# Digital_IO.net
KiCad netlist of a schematic drawn in Altium Designer
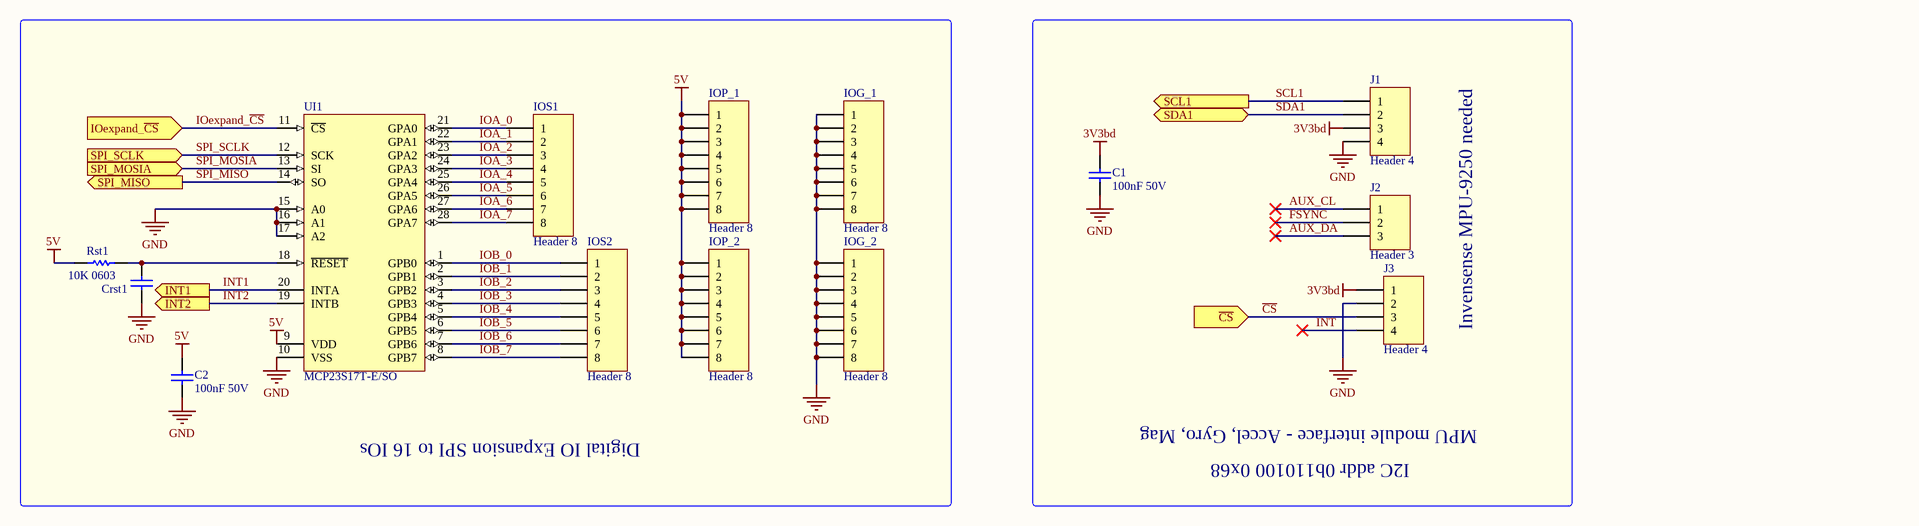
[diagram p0: Digital_IO.SchDoc]

(export (version "E")
  (design (tool "Eeschema 10.0.6"))
  (components
    (comp (ref "C1")
      (value "100nF 50V")
      (footprint "0603C_L")
      (fields
        (field (name "MANUFACTURER") "Yageo")
        (field (name "MANUFACTURER PART NUMBER") "CC0603ZRY5V9BB104")
        (field (name "TOLERANCE") "-20%, +80%")
      )
      (libsource (lib "WCT") (part "Cap101nF_50V_0603"))
    )
    (comp (ref "C2")
      (value "100nF 50V")
      (footprint "0603C_L")
      (fields
        (field (name "MANUFACTURER") "Yageo")
        (field (name "MANUFACTURER PART NUMBER") "CC0603ZRY5V9BB104")
        (field (name "TOLERANCE") "-20%, +80%")
      )
      (libsource (lib "WCT") (part "Cap101nF_50V_0603"))
    )
    (comp (ref "Crst1")
      (value "100nF 50V")
      (footprint "0603C_L")
      (fields
        (field (name "MANUFACTURER") "Yageo")
        (field (name "MANUFACTURER PART NUMBER") "CC0603ZRY5V9BB104")
        (field (name "TOLERANCE") "-20%, +80%")
      )
      (libsource (lib "WCT") (part "Cap100nF_50V_0603"))
    )
    (comp (ref "IOG_1")
      (value "Header 8")
      (footprint "HDR1X8")
      (description "Header, 8-Pin")
      (fields (field (name "PUBLISHER") "Altium Limited"))
      (libsource (lib "Miscellaneous Connectors") (part "Header 8"))
    )
    (comp (ref "IOG_2")
      (value "Header 8")
      (footprint "HDR1X8")
      (description "Header, 8-Pin")
      (fields (field (name "PUBLISHER") "Altium Limited"))
      (libsource (lib "Miscellaneous Connectors") (part "Header 8"))
    )
    (comp (ref "IOP_1")
      (value "Header 8")
      (footprint "HDR1X8")
      (description "Header, 8-Pin")
      (fields (field (name "PUBLISHER") "Altium Limited"))
      (libsource (lib "Miscellaneous Connectors") (part "Header 8"))
    )
    (comp (ref "IOP_2")
      (value "Header 8")
      (footprint "HDR1X8")
      (description "Header, 8-Pin")
      (fields (field (name "PUBLISHER") "Altium Limited"))
      (libsource (lib "Miscellaneous Connectors") (part "Header 8"))
    )
    (comp (ref "IOS1")
      (value "Header 8")
      (footprint "HDR1X8")
      (description "Header, 8-Pin")
      (fields (field (name "PUBLISHER") "Altium Limited"))
      (libsource (lib "Miscellaneous Connectors") (part "Header 8"))
    )
    (comp (ref "IOS2")
      (value "Header 8")
      (footprint "HDR1X8")
      (description "Header, 8-Pin")
      (fields (field (name "PUBLISHER") "Altium Limited"))
      (libsource (lib "Miscellaneous Connectors") (part "Header 8"))
    )
    (comp (ref "J1")
      (value "Header 4")
      (footprint "HDR1X4")
      (description "Header, 4-Pin")
      (fields (field (name "PUBLISHER") "Altium Limited"))
      (libsource (lib "Miscellaneous Connectors") (part "Header 4"))
    )
    (comp (ref "J2")
      (value "Header 3")
      (footprint "HDR1X3")
      (description "Header, 3-Pin")
      (fields (field (name "PUBLISHER") "Altium Limited"))
      (libsource (lib "Miscellaneous Connectors") (part "Header 3"))
    )
    (comp (ref "J3")
      (value "Header 4")
      (footprint "HDR1X4")
      (description "Header, 4-Pin")
      (fields (field (name "PUBLISHER") "Altium Limited"))
      (libsource (lib "Miscellaneous Connectors") (part "Header 4"))
    )
    (comp (ref "Rst1")
      (value "10K 0603")
      (footprint "0603_L")
      (fields
        (field (name "MANUFACTURER") "Panasonic Electronic Components")
        (field (name "MANUFACTURER PART NUMBER") "ERJ-3GEYJ102V")
        (field (name "TOLERANCE") "±5%")
      )
      (libsource (lib "WCT") (part "Res10K_0603"))
    )
    (comp (ref "UI1")
      (value "MCP23S17T-E/SO")
      (footprint "SOIC-SO28_L")
      (description "16-Bit I/O Expander with Serial Interface, 28-Pin SOIC, Extended Temperature, Tape and Reel")
      (libsource (lib "Altium Content Vault") (part "CMP-0186-00131-2"))
    )
  )
  (nets
    (net (code "1") (name "/AUX_CL") (class "Default")
      (node (ref "J2") (pin "1") (pinfunction "1_1") (pintype "passive+no_connect"))
    )
    (net (code "2") (name "/AUX_DA") (class "Default")
      (node (ref "J2") (pin "3") (pinfunction "3_3") (pintype "passive+no_connect"))
    )
    (net (code "3") (name "/FSYNC") (class "Default")
      (node (ref "J2") (pin "2") (pinfunction "2_2") (pintype "passive+no_connect"))
    )
    (net (code "4") (name "/INT") (class "Default")
      (node (ref "J3") (pin "4") (pinfunction "4_4") (pintype "passive+no_connect"))
    )
    (net (code "5") (name "/INT1") (class "Default")
      (node (ref "UI1") (pin "20") (pinfunction "INTA_20") (pintype "open_collector"))
    )
    (net (code "6") (name "/INT2") (class "Default")
      (node (ref "UI1") (pin "19") (pinfunction "INTB_19") (pintype "open_collector"))
    )
    (net (code "7") (name "/IOA_0") (class "Default")
      (node (ref "IOS1") (pin "1") (pinfunction "1_1") (pintype "passive"))
      (node (ref "UI1") (pin "21") (pinfunction "GPA0_21") (pintype "bidirectional"))
    )
    (net (code "8") (name "/IOA_1") (class "Default")
      (node (ref "IOS1") (pin "2") (pinfunction "2_2") (pintype "passive"))
      (node (ref "UI1") (pin "22") (pinfunction "GPA1_22") (pintype "bidirectional"))
    )
    (net (code "9") (name "/IOA_2") (class "Default")
      (node (ref "IOS1") (pin "3") (pinfunction "3_3") (pintype "passive"))
      (node (ref "UI1") (pin "23") (pinfunction "GPA2_23") (pintype "bidirectional"))
    )
    (net (code "10") (name "/IOA_3") (class "Default")
      (node (ref "IOS1") (pin "4") (pinfunction "4_4") (pintype "passive"))
      (node (ref "UI1") (pin "24") (pinfunction "GPA3_24") (pintype "bidirectional"))
    )
    (net (code "11") (name "/IOA_4") (class "Default")
      (node (ref "IOS1") (pin "5") (pinfunction "5_5") (pintype "passive"))
      (node (ref "UI1") (pin "25") (pinfunction "GPA4_25") (pintype "bidirectional"))
    )
    (net (code "12") (name "/IOA_5") (class "Default")
      (node (ref "IOS1") (pin "6") (pinfunction "6_6") (pintype "passive"))
      (node (ref "UI1") (pin "26") (pinfunction "GPA5_26") (pintype "bidirectional"))
    )
    (net (code "13") (name "/IOA_6") (class "Default")
      (node (ref "IOS1") (pin "7") (pinfunction "7_7") (pintype "passive"))
      (node (ref "UI1") (pin "27") (pinfunction "GPA6_27") (pintype "bidirectional"))
    )
    (net (code "14") (name "/IOA_7") (class "Default")
      (node (ref "IOS1") (pin "8") (pinfunction "8_8") (pintype "passive"))
      (node (ref "UI1") (pin "28") (pinfunction "GPA7_28") (pintype "bidirectional"))
    )
    (net (code "15") (name "/IOB_0") (class "Default")
      (node (ref "IOS2") (pin "1") (pinfunction "1_1") (pintype "passive"))
      (node (ref "UI1") (pin "1") (pinfunction "GPB0_1") (pintype "bidirectional"))
    )
    (net (code "16") (name "/IOB_1") (class "Default")
      (node (ref "IOS2") (pin "2") (pinfunction "2_2") (pintype "passive"))
      (node (ref "UI1") (pin "2") (pinfunction "GPB1_2") (pintype "bidirectional"))
    )
    (net (code "17") (name "/IOB_2") (class "Default")
      (node (ref "IOS2") (pin "3") (pinfunction "3_3") (pintype "passive"))
      (node (ref "UI1") (pin "3") (pinfunction "GPB2_3") (pintype "bidirectional"))
    )
    (net (code "18") (name "/IOB_3") (class "Default")
      (node (ref "IOS2") (pin "4") (pinfunction "4_4") (pintype "passive"))
      (node (ref "UI1") (pin "4") (pinfunction "GPB3_4") (pintype "bidirectional"))
    )
    (net (code "19") (name "/IOB_4") (class "Default")
      (node (ref "IOS2") (pin "5") (pinfunction "5_5") (pintype "passive"))
      (node (ref "UI1") (pin "5") (pinfunction "GPB4_5") (pintype "bidirectional"))
    )
    (net (code "20") (name "/IOB_5") (class "Default")
      (node (ref "IOS2") (pin "6") (pinfunction "6_6") (pintype "passive"))
      (node (ref "UI1") (pin "6") (pinfunction "GPB5_6") (pintype "bidirectional"))
    )
    (net (code "21") (name "/IOB_6") (class "Default")
      (node (ref "IOS2") (pin "7") (pinfunction "7_7") (pintype "passive"))
      (node (ref "UI1") (pin "7") (pinfunction "GPB6_7") (pintype "bidirectional"))
    )
    (net (code "22") (name "/IOB_7") (class "Default")
      (node (ref "IOS2") (pin "8") (pinfunction "8_8") (pintype "passive"))
      (node (ref "UI1") (pin "8") (pinfunction "GPB7_8") (pintype "bidirectional"))
    )
    (net (code "23") (name "/IOexpand_~{CS}") (class "Default")
      (node (ref "UI1") (pin "11") (pinfunction "~{CS}_11") (pintype "input"))
    )
    (net (code "24") (name "/SCL1") (class "Default")
      (node (ref "J1") (pin "1") (pinfunction "1_1") (pintype "passive"))
    )
    (net (code "25") (name "/SDA1") (class "Default")
      (node (ref "J1") (pin "2") (pinfunction "2_2") (pintype "passive"))
    )
    (net (code "26") (name "/SPI_MISO") (class "Default")
      (node (ref "UI1") (pin "14") (pinfunction "SO_14") (pintype "bidirectional"))
    )
    (net (code "27") (name "/SPI_MOSIA") (class "Default")
      (node (ref "UI1") (pin "13") (pinfunction "SI_13") (pintype "input"))
    )
    (net (code "28") (name "/SPI_SCLK") (class "Default")
      (node (ref "UI1") (pin "12") (pinfunction "SCK_12") (pintype "input"))
    )
    (net (code "29") (name "/~{CS}") (class "Default")
      (node (ref "J3") (pin "3") (pinfunction "3_3") (pintype "passive"))
    )
    (net (code "30") (name "3V3bd") (class "Default")
      (node (ref "C1") (pin "2") (pinfunction "2_2") (pintype "passive"))
      (node (ref "J1") (pin "3") (pinfunction "3_3") (pintype "passive"))
      (node (ref "J3") (pin "1") (pinfunction "1_1") (pintype "passive"))
    )
    (net (code "31") (name "5V") (class "Default")
      (node (ref "C2") (pin "2") (pinfunction "2_2") (pintype "passive"))
      (node (ref "IOP_1") (pin "1") (pinfunction "1_1") (pintype "passive"))
      (node (ref "IOP_1") (pin "2") (pinfunction "2_2") (pintype "passive"))
      (node (ref "IOP_1") (pin "3") (pinfunction "3_3") (pintype "passive"))
      (node (ref "IOP_1") (pin "4") (pinfunction "4_4") (pintype "passive"))
      (node (ref "IOP_1") (pin "5") (pinfunction "5_5") (pintype "passive"))
      (node (ref "IOP_1") (pin "6") (pinfunction "6_6") (pintype "passive"))
      (node (ref "IOP_1") (pin "7") (pinfunction "7_7") (pintype "passive"))
      (node (ref "IOP_1") (pin "8") (pinfunction "8_8") (pintype "passive"))
      (node (ref "IOP_2") (pin "1") (pinfunction "1_1") (pintype "passive"))
      (node (ref "IOP_2") (pin "2") (pinfunction "2_2") (pintype "passive"))
      (node (ref "IOP_2") (pin "3") (pinfunction "3_3") (pintype "passive"))
      (node (ref "IOP_2") (pin "4") (pinfunction "4_4") (pintype "passive"))
      (node (ref "IOP_2") (pin "5") (pinfunction "5_5") (pintype "passive"))
      (node (ref "IOP_2") (pin "6") (pinfunction "6_6") (pintype "passive"))
      (node (ref "IOP_2") (pin "7") (pinfunction "7_7") (pintype "passive"))
      (node (ref "IOP_2") (pin "8") (pinfunction "8_8") (pintype "passive"))
      (node (ref "Rst1") (pin "2") (pinfunction "2_2") (pintype "passive"))
      (node (ref "UI1") (pin "9") (pinfunction "VDD_9") (pintype "power_in"))
    )
    (net (code "32") (name "GND") (class "Default")
      (node (ref "C1") (pin "1") (pinfunction "1_1") (pintype "passive"))
      (node (ref "C2") (pin "1") (pinfunction "1_1") (pintype "passive"))
      (node (ref "Crst1") (pin "1") (pinfunction "1_1") (pintype "passive"))
      (node (ref "IOG_1") (pin "1") (pinfunction "1_1") (pintype "passive"))
      (node (ref "IOG_1") (pin "2") (pinfunction "2_2") (pintype "passive"))
      (node (ref "IOG_1") (pin "3") (pinfunction "3_3") (pintype "passive"))
      (node (ref "IOG_1") (pin "4") (pinfunction "4_4") (pintype "passive"))
      (node (ref "IOG_1") (pin "5") (pinfunction "5_5") (pintype "passive"))
      (node (ref "IOG_1") (pin "6") (pinfunction "6_6") (pintype "passive"))
      (node (ref "IOG_1") (pin "7") (pinfunction "7_7") (pintype "passive"))
      (node (ref "IOG_1") (pin "8") (pinfunction "8_8") (pintype "passive"))
      (node (ref "IOG_2") (pin "1") (pinfunction "1_1") (pintype "passive"))
      (node (ref "IOG_2") (pin "2") (pinfunction "2_2") (pintype "passive"))
      (node (ref "IOG_2") (pin "3") (pinfunction "3_3") (pintype "passive"))
      (node (ref "IOG_2") (pin "4") (pinfunction "4_4") (pintype "passive"))
      (node (ref "IOG_2") (pin "5") (pinfunction "5_5") (pintype "passive"))
      (node (ref "IOG_2") (pin "6") (pinfunction "6_6") (pintype "passive"))
      (node (ref "IOG_2") (pin "7") (pinfunction "7_7") (pintype "passive"))
      (node (ref "IOG_2") (pin "8") (pinfunction "8_8") (pintype "passive"))
      (node (ref "J1") (pin "4") (pinfunction "4_4") (pintype "passive"))
      (node (ref "J3") (pin "2") (pinfunction "2_2") (pintype "passive"))
      (node (ref "UI1") (pin "10") (pinfunction "VSS_10") (pintype "power_in"))
      (node (ref "UI1") (pin "15") (pinfunction "A0_15") (pintype "input"))
      (node (ref "UI1") (pin "16") (pinfunction "A1_16") (pintype "input"))
      (node (ref "UI1") (pin "17") (pinfunction "A2_17") (pintype "input"))
    )
    (net (code "33") (name "Net-(UI1-~{RESET})") (class "Default")
      (node (ref "Crst1") (pin "2") (pinfunction "2_2") (pintype "passive"))
      (node (ref "Rst1") (pin "1") (pinfunction "1_1") (pintype "passive"))
      (node (ref "UI1") (pin "18") (pinfunction "~{RESET}_18") (pintype "input"))
    )
  )
)
